# step.net
KiCad netlist of a schematic drawn in Altium Designer
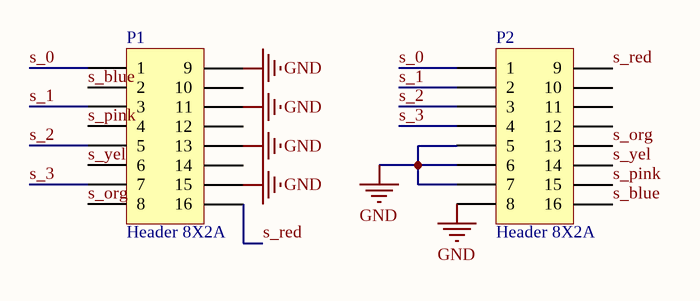
[diagram p0: step.SchDoc]

(export (version "E")
  (design (tool "Eeschema 10.0.6"))
  (components
    (comp (ref "P1")
      (value "Header 8X2A")
      (footprint "DIP-16")
      (description "Header, 8-Pin, Dual row")
      (fields (field (name "PUBLISHER") "Altium Limited"))
      (libsource (lib "Miscellaneous Connectors") (part "Header 8X2A"))
    )
    (comp (ref "P2")
      (value "Header 8X2A")
      (footprint "DIP-16")
      (description "Header, 8-Pin, Dual row")
      (fields (field (name "PUBLISHER") "Altium Limited"))
      (libsource (lib "Miscellaneous Connectors") (part "Header 8X2A"))
    )
  )
  (nets
    (net (code "1") (name "/s_0") (class "Default")
      (node (ref "P1") (pin "1") (pinfunction "1_1") (pintype "passive"))
      (node (ref "P2") (pin "1") (pinfunction "1_1") (pintype "passive"))
    )
    (net (code "2") (name "/s_1") (class "Default")
      (node (ref "P1") (pin "3") (pinfunction "3_3") (pintype "passive"))
      (node (ref "P2") (pin "2") (pinfunction "2_2") (pintype "passive"))
    )
    (net (code "3") (name "/s_2") (class "Default")
      (node (ref "P1") (pin "5") (pinfunction "5_5") (pintype "passive"))
      (node (ref "P2") (pin "3") (pinfunction "3_3") (pintype "passive"))
    )
    (net (code "4") (name "/s_3") (class "Default")
      (node (ref "P1") (pin "7") (pinfunction "7_7") (pintype "passive"))
      (node (ref "P2") (pin "4") (pinfunction "4_4") (pintype "passive"))
    )
    (net (code "5") (name "/s_blue") (class "Default")
      (node (ref "P1") (pin "2") (pinfunction "2_2") (pintype "passive"))
      (node (ref "P2") (pin "16") (pinfunction "16_16") (pintype "passive"))
    )
    (net (code "6") (name "/s_org") (class "Default")
      (node (ref "P1") (pin "8") (pinfunction "8_8") (pintype "passive"))
      (node (ref "P2") (pin "13") (pinfunction "13_13") (pintype "passive"))
    )
    (net (code "7") (name "/s_pink") (class "Default")
      (node (ref "P1") (pin "4") (pinfunction "4_4") (pintype "passive"))
      (node (ref "P2") (pin "15") (pinfunction "15_15") (pintype "passive"))
    )
    (net (code "8") (name "/s_red") (class "Default")
      (node (ref "P1") (pin "16") (pinfunction "16_16") (pintype "passive"))
      (node (ref "P2") (pin "9") (pinfunction "9_9") (pintype "passive"))
    )
    (net (code "9") (name "/s_yel") (class "Default")
      (node (ref "P1") (pin "6") (pinfunction "6_6") (pintype "passive"))
      (node (ref "P2") (pin "14") (pinfunction "14_14") (pintype "passive"))
    )
    (net (code "10") (name "GND") (class "Default")
      (node (ref "P1") (pin "11") (pinfunction "11_11") (pintype "passive"))
      (node (ref "P1") (pin "13") (pinfunction "13_13") (pintype "passive"))
      (node (ref "P1") (pin "15") (pinfunction "15_15") (pintype "passive"))
      (node (ref "P1") (pin "9") (pinfunction "9_9") (pintype "passive"))
      (node (ref "P2") (pin "5") (pinfunction "5_5") (pintype "passive"))
      (node (ref "P2") (pin "6") (pinfunction "6_6") (pintype "passive"))
      (node (ref "P2") (pin "7") (pinfunction "7_7") (pintype "passive"))
      (node (ref "P2") (pin "8") (pinfunction "8_8") (pintype "passive"))
    )
    (net (code "11") (name "unconnected-(P1-Pad10)") (class "Default")
      (node (ref "P1") (pin "10") (pinfunction "10_10") (pintype "passive"))
    )
    (net (code "12") (name "unconnected-(P1-Pad12)") (class "Default")
      (node (ref "P1") (pin "12") (pinfunction "12_12") (pintype "passive"))
    )
    (net (code "13") (name "unconnected-(P1-Pad14)") (class "Default")
      (node (ref "P1") (pin "14") (pinfunction "14_14") (pintype "passive"))
    )
    (net (code "14") (name "unconnected-(P2-Pad10)") (class "Default")
      (node (ref "P2") (pin "10") (pinfunction "10_10") (pintype "passive"))
    )
    (net (code "15") (name "unconnected-(P2-Pad11)") (class "Default")
      (node (ref "P2") (pin "11") (pinfunction "11_11") (pintype "passive"))
    )
    (net (code "16") (name "unconnected-(P2-Pad12)") (class "Default")
      (node (ref "P2") (pin "12") (pinfunction "12_12") (pintype "passive"))
    )
  )
)
